# 1-Schematic_PCB_Hacker_Card.net
KiCad netlist of a schematic drawn in EasyEDA
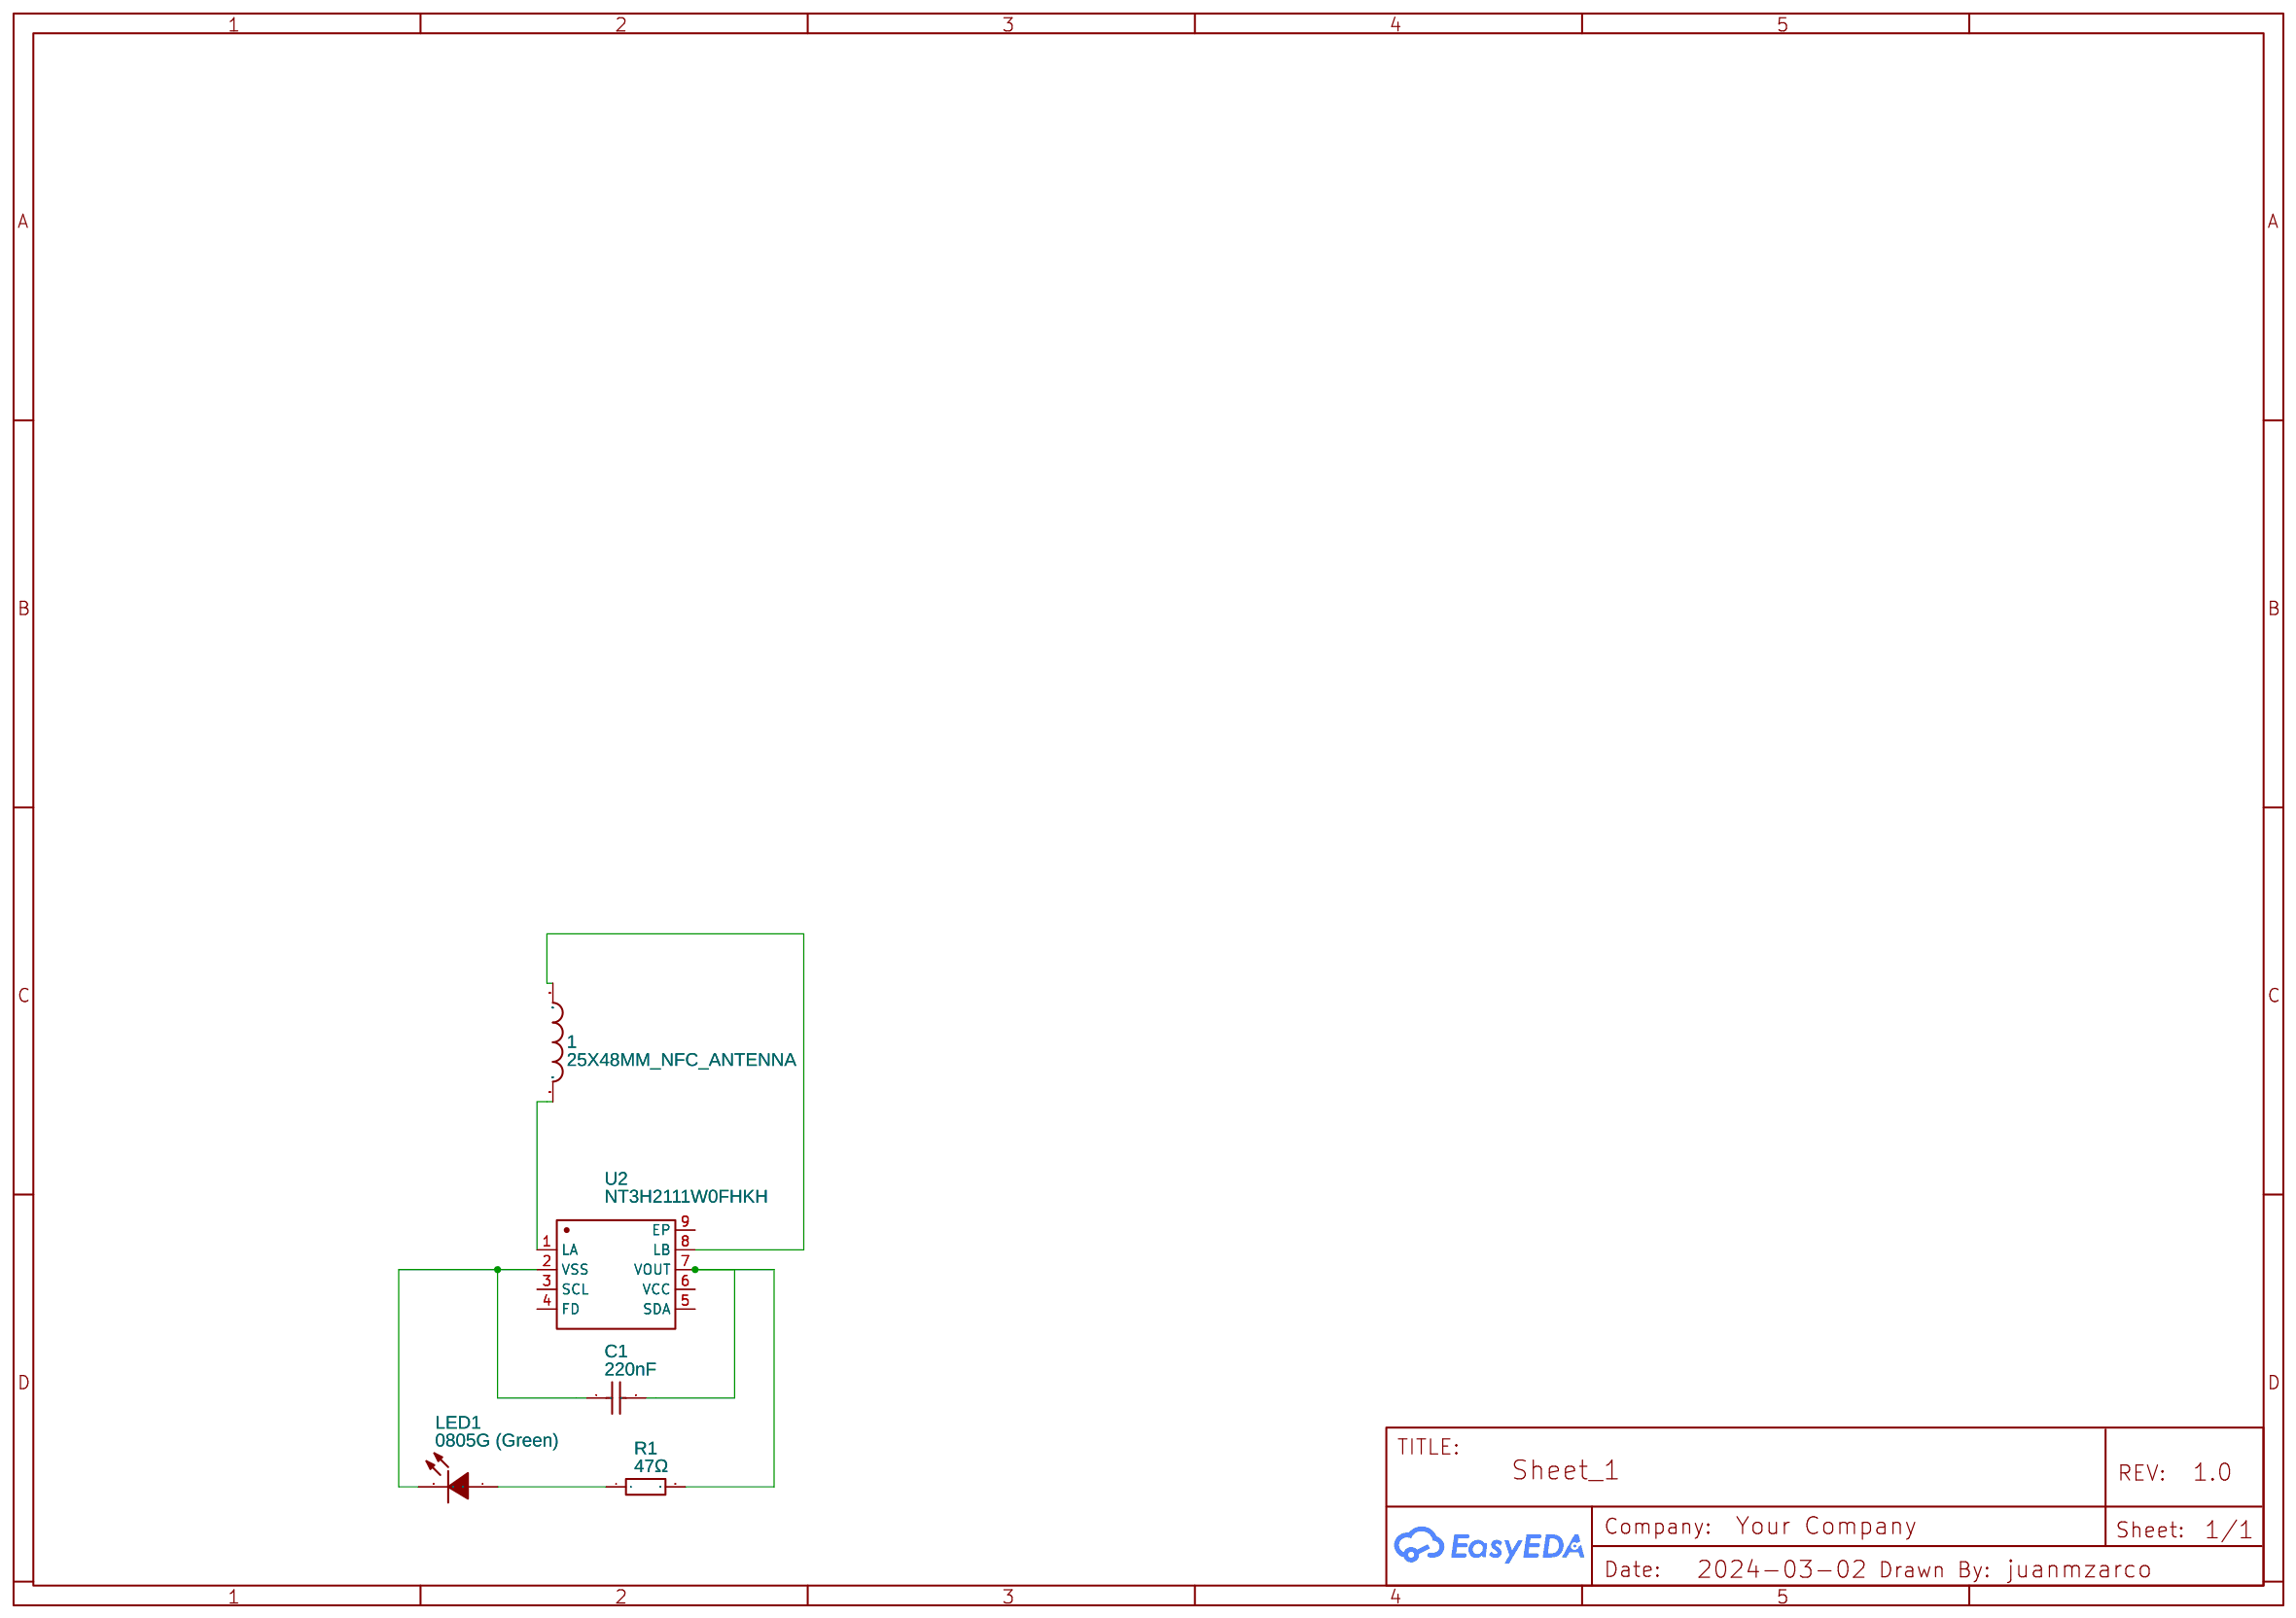
[diagram p0: schematic sheet]

(export (version "E")
  (design (tool "Eeschema 10.0.6"))
  (components
    (comp (ref "1") (value "25X48MM_NFC_ANTENNA") (libsource (lib "") (part "25X48MM_NFC_ANTENNA")))
    (comp (ref "C1")
      (value "220nF")
      (fields
        (field (name "Manufacturer Part") "CL10B224KA8NNNC")
        (field (name "Manufacturer") "SAMSUNG(三星)")
      )
      (libsource (lib "") (part "CL10B224KA8NNNC"))
    )
    (comp (ref "LED1")
      (value "0805G (Green)")
      (fields (field (name "Manufacturer Part") "KT-0805G") (field (name "Manufacturer") "KENTO"))
      (libsource (lib "") (part "0805G (Green)"))
    )
    (comp (ref "R1")
      (value "47Ω")
      (fields
        (field (name "Manufacturer Part") "0603WAF470JT5E")
        (field (name "Manufacturer") "UNI-ROYAL(厚声)")
      )
      (libsource (lib "") (part "0603WAF470JT5E"))
    )
    (comp (ref "U2")
      (value "NT3H2111W0FHKH")
      (fields (field (name "Manufacturer") "NXP(恩智浦)"))
      (libsource (lib "") (part "NT3H2111W0FHKH"))
    )
  )
  (nets
    (net (code "1") (name "Net-(LED1-A)") (class "Default")
      (node (ref "LED1") (pin "1") (pinfunction "A_1") (pintype "unspecified"))
      (node (ref "R1") (pin "1") (pinfunction "1_1") (pintype "input"))
    )
    (net (code "2") (name "Net-(LED1-K)") (class "Default")
      (node (ref "C1") (pin "1") (pinfunction "1_1") (pintype "input"))
      (node (ref "LED1") (pin "2") (pinfunction "K_2") (pintype "unspecified"))
      (node (ref "U2") (pin "2") (pinfunction "VSS_2") (pintype "unspecified"))
    )
    (net (code "3") (name "Net-(U2-LA)") (class "Default")
      (node (ref "1") (pin "P$2") (pinfunction "P$2_P$2") (pintype "bidirectional"))
      (node (ref "U2") (pin "1") (pinfunction "LA_1") (pintype "unspecified"))
    )
    (net (code "4") (name "Net-(U2-LB)") (class "Default")
      (node (ref "1") (pin "P$1") (pinfunction "P$1_P$1") (pintype "bidirectional"))
      (node (ref "U2") (pin "8") (pinfunction "LB_8") (pintype "unspecified"))
    )
    (net (code "5") (name "Net-(U2-VOUT)") (class "Default")
      (node (ref "C1") (pin "2") (pinfunction "2_2") (pintype "input"))
      (node (ref "R1") (pin "2") (pinfunction "2_2") (pintype "input"))
      (node (ref "U2") (pin "7") (pinfunction "VOUT_7") (pintype "unspecified"))
    )
    (net (code "6") (name "unconnected-(U2-EP-Pad9)") (class "Default")
      (node (ref "U2") (pin "9") (pinfunction "EP_9") (pintype "unspecified"))
    )
    (net (code "7") (name "unconnected-(U2-FD-Pad4)") (class "Default")
      (node (ref "U2") (pin "4") (pinfunction "FD_4") (pintype "unspecified"))
    )
    (net (code "8") (name "unconnected-(U2-SCL-Pad3)") (class "Default")
      (node (ref "U2") (pin "3") (pinfunction "SCL_3") (pintype "unspecified"))
    )
    (net (code "9") (name "unconnected-(U2-SDA-Pad5)") (class "Default")
      (node (ref "U2") (pin "5") (pinfunction "SDA_5") (pintype "unspecified"))
    )
    (net (code "10") (name "unconnected-(U2-VCC-Pad6)") (class "Default")
      (node (ref "U2") (pin "6") (pinfunction "VCC_6") (pintype "unspecified"))
    )
  )
)
